# TKeyboard_2021-06-17.net
KiCad netlist of a schematic drawn in Altium Designer
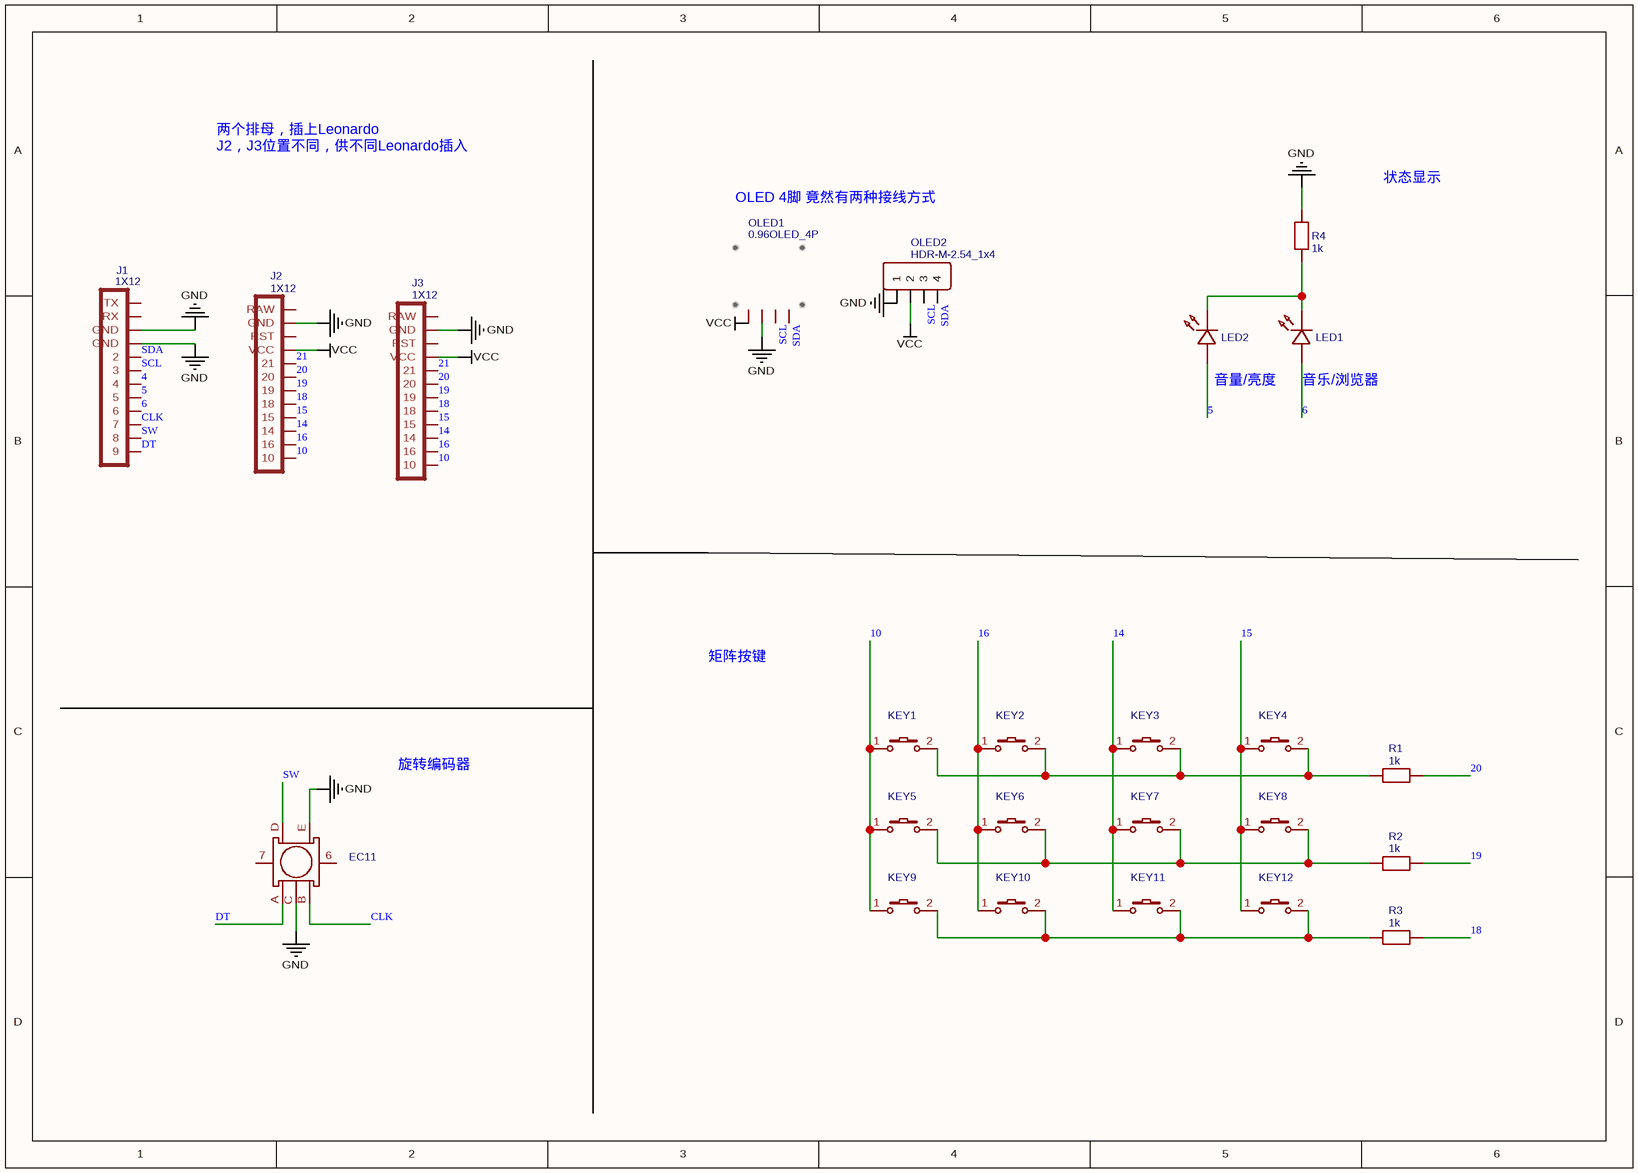
[diagram p0: TKeyboard_2021-06-17.schdoc]

(export (version "E")
  (design (tool "Eeschema 10.0.6"))
  (components
    (comp (ref "EC11")
      (value "EC11E152T409")
      (fields (field (name "BOM_SUPPLIER PART") "C110314") (field (name "CONTRIBUTOR") "LCSC"))
      (libsource (lib "altium-import") (part "root_0_EC11E152T409_"))
    )
    (comp (ref "J1") (value "1X12") (libsource (lib "altium-import") (part "root_0_1X12_")))
    (comp (ref "J2") (value "1X12") (libsource (lib "altium-import") (part "root_0_1X12_")))
    (comp (ref "J3") (value "1X12") (libsource (lib "altium-import") (part "root_0_1X12_")))
    (comp (ref "KEY1")
      (value "K2-3.6×6.1_SMD")
      (fields
        (field (name "BOM_SUPPLIER PART") "C118141")
        (field (name "BOM_MANUFACTURER PART") "K2-1107ST-A4SW-06")
        (field (name "CONTRIBUTOR") "LCEDA_Lib")
      )
      (libsource (lib "altium-import") (part "root_0_K2-3.6×6.1_SMD_"))
    )
    (comp (ref "KEY2")
      (value "K2-3.6×6.1_SMD")
      (fields
        (field (name "BOM_SUPPLIER PART") "C118141")
        (field (name "BOM_MANUFACTURER PART") "K2-1107ST-A4SW-06")
        (field (name "CONTRIBUTOR") "LCEDA_Lib")
      )
      (libsource (lib "altium-import") (part "root_0_K2-3.6×6.1_SMD_"))
    )
    (comp (ref "KEY3")
      (value "K2-3.6×6.1_SMD")
      (fields
        (field (name "BOM_SUPPLIER PART") "C118141")
        (field (name "BOM_MANUFACTURER PART") "K2-1107ST-A4SW-06")
        (field (name "CONTRIBUTOR") "LCEDA_Lib")
      )
      (libsource (lib "altium-import") (part "root_0_K2-3.6×6.1_SMD_"))
    )
    (comp (ref "KEY4")
      (value "K2-3.6×6.1_SMD")
      (fields
        (field (name "BOM_SUPPLIER PART") "C118141")
        (field (name "BOM_MANUFACTURER PART") "K2-1107ST-A4SW-06")
        (field (name "CONTRIBUTOR") "LCEDA_Lib")
      )
      (libsource (lib "altium-import") (part "root_0_K2-3.6×6.1_SMD_"))
    )
    (comp (ref "KEY5")
      (value "K2-3.6×6.1_SMD")
      (fields
        (field (name "BOM_SUPPLIER PART") "C118141")
        (field (name "BOM_MANUFACTURER PART") "K2-1107ST-A4SW-06")
        (field (name "CONTRIBUTOR") "LCEDA_Lib")
      )
      (libsource (lib "altium-import") (part "root_0_K2-3.6×6.1_SMD_"))
    )
    (comp (ref "KEY6")
      (value "K2-3.6×6.1_SMD")
      (fields
        (field (name "BOM_SUPPLIER PART") "C118141")
        (field (name "BOM_MANUFACTURER PART") "K2-1107ST-A4SW-06")
        (field (name "CONTRIBUTOR") "LCEDA_Lib")
      )
      (libsource (lib "altium-import") (part "root_0_K2-3.6×6.1_SMD_"))
    )
    (comp (ref "KEY7")
      (value "K2-3.6×6.1_SMD")
      (fields
        (field (name "BOM_SUPPLIER PART") "C118141")
        (field (name "BOM_MANUFACTURER PART") "K2-1107ST-A4SW-06")
        (field (name "CONTRIBUTOR") "LCEDA_Lib")
      )
      (libsource (lib "altium-import") (part "root_0_K2-3.6×6.1_SMD_"))
    )
    (comp (ref "KEY8")
      (value "K2-3.6×6.1_SMD")
      (fields
        (field (name "BOM_SUPPLIER PART") "C118141")
        (field (name "BOM_MANUFACTURER PART") "K2-1107ST-A4SW-06")
        (field (name "CONTRIBUTOR") "LCEDA_Lib")
      )
      (libsource (lib "altium-import") (part "root_0_K2-3.6×6.1_SMD_"))
    )
    (comp (ref "KEY9")
      (value "K2-3.6×6.1_SMD")
      (fields
        (field (name "BOM_SUPPLIER PART") "C118141")
        (field (name "BOM_MANUFACTURER PART") "K2-1107ST-A4SW-06")
        (field (name "CONTRIBUTOR") "LCEDA_Lib")
      )
      (libsource (lib "altium-import") (part "root_0_K2-3.6×6.1_SMD_"))
    )
    (comp (ref "KEY10")
      (value "K2-3.6×6.1_SMD")
      (fields
        (field (name "BOM_SUPPLIER PART") "C118141")
        (field (name "BOM_MANUFACTURER PART") "K2-1107ST-A4SW-06")
        (field (name "CONTRIBUTOR") "LCEDA_Lib")
      )
      (libsource (lib "altium-import") (part "root_0_K2-3.6×6.1_SMD_"))
    )
    (comp (ref "KEY11")
      (value "K2-3.6×6.1_SMD")
      (fields
        (field (name "BOM_SUPPLIER PART") "C118141")
        (field (name "BOM_MANUFACTURER PART") "K2-1107ST-A4SW-06")
        (field (name "CONTRIBUTOR") "LCEDA_Lib")
      )
      (libsource (lib "altium-import") (part "root_0_K2-3.6×6.1_SMD_"))
    )
    (comp (ref "KEY12")
      (value "K2-3.6×6.1_SMD")
      (fields
        (field (name "BOM_SUPPLIER PART") "C118141")
        (field (name "BOM_MANUFACTURER PART") "K2-1107ST-A4SW-06")
        (field (name "CONTRIBUTOR") "LCEDA_Lib")
      )
      (libsource (lib "altium-import") (part "root_0_K2-3.6×6.1_SMD_"))
    )
    (comp (ref "LED1")
      (value "LED-0603_R")
      (fields
        (field (name "BOM_MANUFACTURER PART") "19-217/R6C-AL1M2VY/3T")
        (field (name "BOM_SUPPLIER PART") "C72044")
        (field (name "CONTRIBUTOR") "LCEDA_01")
      )
      (libsource (lib "altium-import") (part "root_1_LED-0603_R_"))
    )
    (comp (ref "LED2")
      (value "LED-0603_R")
      (fields
        (field (name "BOM_MANUFACTURER PART") "19-217/R6C-AL1M2VY/3T")
        (field (name "BOM_SUPPLIER PART") "C72044")
        (field (name "CONTRIBUTOR") "LCEDA_01")
      )
      (libsource (lib "altium-import") (part "root_1_LED-0603_R_"))
    )
    (comp (ref "OLED1")
      (value "0.96OLED_4P")
      (fields (field (name "CONTRIBUTOR") "LCEDA_Lib"))
      (libsource (lib "altium-import") (part "root_0_0.96OLED_4P_"))
    )
    (comp (ref "OLED2")
      (value "HDR-M-2.54_1x4")
      (fields (field (name "BOM_SUPPLIER PART") "C124378") (field (name "CONTRIBUTOR") "LCEDA_Lib"))
      (libsource (lib "altium-import") (part "root_1_HDR-M-2.54_1x4_"))
    )
    (comp (ref "R1")
      (value "1k")
      (fields (field (name "CONTRIBUTOR") "LCEDA_Lib"))
      (libsource (lib "altium-import") (part "root_0_1k_"))
    )
    (comp (ref "R2")
      (value "1k")
      (fields (field (name "CONTRIBUTOR") "LCEDA_Lib"))
      (libsource (lib "altium-import") (part "root_0_1k_"))
    )
    (comp (ref "R3")
      (value "1k")
      (fields (field (name "CONTRIBUTOR") "LCEDA_Lib"))
      (libsource (lib "altium-import") (part "root_0_1k_"))
    )
    (comp (ref "R4")
      (value "1k")
      (fields (field (name "CONTRIBUTOR") "LCEDA_Lib"))
      (libsource (lib "altium-import") (part "root_1_1k_"))
    )
  )
  (nets
    (net (code "1") (name "/4") (class "Default")
      (node (ref "J1") (pin "6") (pinfunction "4_6") (pintype "passive"))
    )
    (net (code "2") (name "/5") (class "Default")
      (node (ref "J1") (pin "5") (pinfunction "5_5") (pintype "passive"))
      (node (ref "LED2") (pin "1") (pinfunction "1_1") (pintype "passive"))
    )
    (net (code "3") (name "/6") (class "Default")
      (node (ref "J1") (pin "4") (pinfunction "6_4") (pintype "passive"))
      (node (ref "LED1") (pin "1") (pinfunction "1_1") (pintype "passive"))
    )
    (net (code "4") (name "/10") (class "Default")
      (node (ref "J2") (pin "1") (pinfunction "9_1") (pintype "passive"))
      (node (ref "J3") (pin "1") (pinfunction "9_1") (pintype "passive"))
      (node (ref "KEY1") (pin "1") (pinfunction "1_1") (pintype "passive"))
      (node (ref "KEY5") (pin "1") (pinfunction "1_1") (pintype "passive"))
      (node (ref "KEY9") (pin "1") (pinfunction "1_1") (pintype "passive"))
    )
    (net (code "5") (name "/14") (class "Default")
      (node (ref "J2") (pin "3") (pinfunction "7_3") (pintype "passive"))
      (node (ref "J3") (pin "3") (pinfunction "7_3") (pintype "passive"))
      (node (ref "KEY11") (pin "1") (pinfunction "1_1") (pintype "passive"))
      (node (ref "KEY3") (pin "1") (pinfunction "1_1") (pintype "passive"))
      (node (ref "KEY7") (pin "1") (pinfunction "1_1") (pintype "passive"))
    )
    (net (code "6") (name "/15") (class "Default")
      (node (ref "J2") (pin "4") (pinfunction "6_4") (pintype "passive"))
      (node (ref "J3") (pin "4") (pinfunction "6_4") (pintype "passive"))
      (node (ref "KEY12") (pin "1") (pinfunction "1_1") (pintype "passive"))
      (node (ref "KEY4") (pin "1") (pinfunction "1_1") (pintype "passive"))
      (node (ref "KEY8") (pin "1") (pinfunction "1_1") (pintype "passive"))
    )
    (net (code "7") (name "/16") (class "Default")
      (node (ref "J2") (pin "2") (pinfunction "8_2") (pintype "passive"))
      (node (ref "J3") (pin "2") (pinfunction "8_2") (pintype "passive"))
      (node (ref "KEY10") (pin "1") (pinfunction "1_1") (pintype "passive"))
      (node (ref "KEY2") (pin "1") (pinfunction "1_1") (pintype "passive"))
      (node (ref "KEY6") (pin "1") (pinfunction "1_1") (pintype "passive"))
    )
    (net (code "8") (name "/18") (class "Default")
      (node (ref "J2") (pin "5") (pinfunction "5_5") (pintype "passive"))
      (node (ref "J3") (pin "5") (pinfunction "5_5") (pintype "passive"))
      (node (ref "R3") (pin "2") (pinfunction "2_2") (pintype "passive"))
    )
    (net (code "9") (name "/19") (class "Default")
      (node (ref "J2") (pin "6") (pinfunction "4_6") (pintype "passive"))
      (node (ref "J3") (pin "6") (pinfunction "4_6") (pintype "passive"))
      (node (ref "R2") (pin "2") (pinfunction "2_2") (pintype "passive"))
    )
    (net (code "10") (name "/20") (class "Default")
      (node (ref "J2") (pin "7") (pinfunction "3_7") (pintype "passive"))
      (node (ref "J3") (pin "7") (pinfunction "3_7") (pintype "passive"))
      (node (ref "R1") (pin "2") (pinfunction "2_2") (pintype "passive"))
    )
    (net (code "11") (name "/21") (class "Default")
      (node (ref "J2") (pin "8") (pinfunction "2_8") (pintype "passive"))
      (node (ref "J3") (pin "8") (pinfunction "2_8") (pintype "passive"))
    )
    (net (code "12") (name "/CLK") (class "Default")
      (node (ref "EC11") (pin "B") (pinfunction "B_B") (pintype "passive"))
      (node (ref "J1") (pin "3") (pinfunction "7_3") (pintype "passive"))
    )
    (net (code "13") (name "/DT") (class "Default")
      (node (ref "EC11") (pin "A") (pinfunction "A_A") (pintype "passive"))
      (node (ref "J1") (pin "1") (pinfunction "9_1") (pintype "passive"))
    )
    (net (code "14") (name "/SCL") (class "Default")
      (node (ref "J1") (pin "7") (pinfunction "3_7") (pintype "passive"))
      (node (ref "OLED1") (pin "3") (pinfunction "3_3") (pintype "passive"))
      (node (ref "OLED2") (pin "3") (pinfunction "3_3") (pintype "passive"))
    )
    (net (code "15") (name "/SDA") (class "Default")
      (node (ref "J1") (pin "8") (pinfunction "2_8") (pintype "passive"))
      (node (ref "OLED1") (pin "4") (pinfunction "4_4") (pintype "passive"))
      (node (ref "OLED2") (pin "4") (pinfunction "4_4") (pintype "passive"))
    )
    (net (code "16") (name "/SW") (class "Default")
      (node (ref "EC11") (pin "D") (pinfunction "D_D") (pintype "passive"))
      (node (ref "J1") (pin "2") (pinfunction "8_2") (pintype "passive"))
    )
    (net (code "17") (name "GND") (class "Default")
      (node (ref "EC11") (pin "C") (pinfunction "C_C") (pintype "passive"))
      (node (ref "EC11") (pin "E") (pinfunction "E_E") (pintype "passive"))
      (node (ref "J1") (pin "10") (pinfunction "GND_10") (pintype "passive"))
      (node (ref "J1") (pin "9") (pinfunction "GND_9") (pintype "passive"))
      (node (ref "J2") (pin "11") (pinfunction "RX_11") (pintype "passive"))
      (node (ref "J3") (pin "11") (pinfunction "RX_11") (pintype "passive"))
      (node (ref "OLED1") (pin "2") (pinfunction "2_2") (pintype "passive"))
      (node (ref "OLED2") (pin "1") (pinfunction "1_1") (pintype "passive"))
      (node (ref "R4") (pin "2") (pinfunction "2_2") (pintype "passive"))
    )
    (net (code "18") (name "Net-(KEY1-Pad2)") (class "Default")
      (node (ref "KEY1") (pin "2") (pinfunction "2_2") (pintype "passive"))
      (node (ref "KEY2") (pin "2") (pinfunction "2_2") (pintype "passive"))
      (node (ref "KEY3") (pin "2") (pinfunction "2_2") (pintype "passive"))
      (node (ref "KEY4") (pin "2") (pinfunction "2_2") (pintype "passive"))
      (node (ref "R1") (pin "1") (pinfunction "1_1") (pintype "passive"))
    )
    (net (code "19") (name "Net-(KEY5-Pad2)") (class "Default")
      (node (ref "KEY5") (pin "2") (pinfunction "2_2") (pintype "passive"))
      (node (ref "KEY6") (pin "2") (pinfunction "2_2") (pintype "passive"))
      (node (ref "KEY7") (pin "2") (pinfunction "2_2") (pintype "passive"))
      (node (ref "KEY8") (pin "2") (pinfunction "2_2") (pintype "passive"))
      (node (ref "R2") (pin "1") (pinfunction "1_1") (pintype "passive"))
    )
    (net (code "20") (name "Net-(KEY10-Pad2)") (class "Default")
      (node (ref "KEY10") (pin "2") (pinfunction "2_2") (pintype "passive"))
      (node (ref "KEY11") (pin "2") (pinfunction "2_2") (pintype "passive"))
      (node (ref "KEY12") (pin "2") (pinfunction "2_2") (pintype "passive"))
      (node (ref "KEY9") (pin "2") (pinfunction "2_2") (pintype "passive"))
      (node (ref "R3") (pin "1") (pinfunction "1_1") (pintype "passive"))
    )
    (net (code "21") (name "Net-(LED1-Pad2)") (class "Default")
      (node (ref "LED1") (pin "2") (pinfunction "2_2") (pintype "passive"))
      (node (ref "LED2") (pin "2") (pinfunction "2_2") (pintype "passive"))
      (node (ref "R4") (pin "1") (pinfunction "1_1") (pintype "passive"))
    )
    (net (code "22") (name "VCC") (class "Default")
      (node (ref "J2") (pin "9") (pinfunction "GND_9") (pintype "passive"))
      (node (ref "J3") (pin "9") (pinfunction "GND_9") (pintype "passive"))
      (node (ref "OLED1") (pin "1") (pinfunction "1_1") (pintype "passive"))
      (node (ref "OLED2") (pin "2") (pinfunction "2_2") (pintype "passive"))
    )
    (net (code "23") (name "unconnected-(EC11-Pad6)") (class "Default")
      (node (ref "EC11") (pin "6") (pinfunction "6_6") (pintype "passive"))
    )
    (net (code "24") (name "unconnected-(EC11-Pad7)") (class "Default")
      (node (ref "EC11") (pin "7") (pinfunction "7_7") (pintype "passive"))
    )
    (net (code "25") (name "unconnected-(J1-RX-Pad11)") (class "Default")
      (node (ref "J1") (pin "11") (pinfunction "RX_11") (pintype "passive"))
    )
    (net (code "26") (name "unconnected-(J1-TX-Pad12)") (class "Default")
      (node (ref "J1") (pin "12") (pinfunction "TX_12") (pintype "passive"))
    )
    (net (code "27") (name "unconnected-(J2-GND-Pad10)") (class "Default")
      (node (ref "J2") (pin "10") (pinfunction "GND_10") (pintype "passive"))
    )
    (net (code "28") (name "unconnected-(J2-TX-Pad12)") (class "Default")
      (node (ref "J2") (pin "12") (pinfunction "TX_12") (pintype "passive"))
    )
    (net (code "29") (name "unconnected-(J3-GND-Pad10)") (class "Default")
      (node (ref "J3") (pin "10") (pinfunction "GND_10") (pintype "passive"))
    )
    (net (code "30") (name "unconnected-(J3-TX-Pad12)") (class "Default")
      (node (ref "J3") (pin "12") (pinfunction "TX_12") (pintype "passive"))
    )
  )
)
